# structure_thermometer.net
KiCad netlist of a schematic drawn in Altium Designer
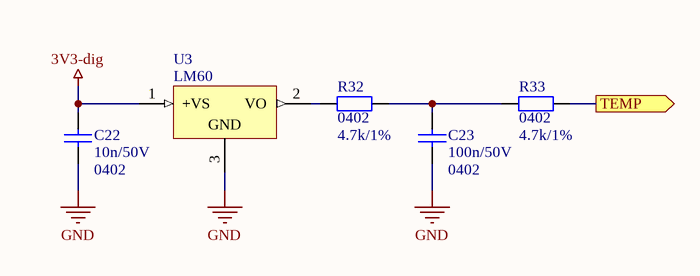
[diagram p0: structure_thermometer.SchDoc]

(export (version "E")
  (design (tool "Eeschema 10.0.6"))
  (components
    (comp (ref "C22")
      (value "10n/50V")
      (footprint "SMD_Capacitor_0402")
      (description "Ceramic Cap Kemet COTS 10n/50V X7R 0402")
      (fields
        (field (name "MANUFACTURERPARTNUMBER") "C0402T103K5RALTU")
        (field (name "MANUFACTURER") "Kemet")
        (field (name "PACKAGE") "0402")
      )
      (libsource (lib "capacitors") (part "Cer_C0402T103K5RALTU"))
    )
    (comp (ref "C23")
      (value "100n/50V")
      (footprint "SMD_Capacitor_0402")
      (description "Ceramic Cap Kemet COTS 10n/50V X7R 0402")
      (fields
        (field (name "MANUFACTURERPARTNUMBER") "C0402T103K5RALTU")
        (field (name "MANUFACTURER") "Kemet")
        (field (name "PACKAGE") "0402")
      )
      (libsource (lib "capacitors") (part "Cer_C0402T103K5RALTU"))
    )
    (comp (ref "R32")
      (value "4.7k/1%")
      (footprint "SMD_Resistor_0402")
      (description "4.7k/1% Vishay CRCW 0402 Resistor. 63mW, 100ppm, 50V.")
      (fields
        (field (name "MANUFACTURERPARTNUMBER") "CRCW04024K70FKxxxx")
        (field (name "MANUFACTURER") "Vishay")
        (field (name "PACKAGE") "0402")
      )
      (libsource (lib "resistors") (part "CRCW04024K70FKxxxx"))
    )
    (comp (ref "R33")
      (value "4.7k/1%")
      (footprint "SMD_Resistor_0402")
      (description "4.7k/1% Vishay CRCW 0402 Resistor. 63mW, 100ppm, 50V.")
      (fields
        (field (name "MANUFACTURERPARTNUMBER") "CRCW04024K70FKxxxx")
        (field (name "MANUFACTURER") "Vishay")
        (field (name "PACKAGE") "0402")
      )
      (libsource (lib "resistors") (part "CRCW04024K70FKxxxx"))
    )
    (comp (ref "U3")
      (value "LM60")
      (footprint "SOT23-3")
      (description "Analog temperature sensor")
      (libsource (lib "microcircuits") (part "LM60"))
    )
  )
  (nets
    (net (code "1") (name "/TEMP") (class "Default")
      (node (ref "R33") (pin "2") (pinfunction "2_2") (pintype "passive"))
    )
    (net (code "2") (name "3V3-dig") (class "Default")
      (node (ref "C22") (pin "1") (pinfunction "1_1") (pintype "passive"))
      (node (ref "U3") (pin "1") (pinfunction "+VS_1") (pintype "input"))
    )
    (net (code "3") (name "GND") (class "Default")
      (node (ref "C22") (pin "2") (pinfunction "2_2") (pintype "passive"))
      (node (ref "C23") (pin "2") (pinfunction "2_2") (pintype "passive"))
      (node (ref "U3") (pin "3") (pinfunction "GND_3") (pintype "power_in"))
    )
    (net (code "4") (name "Net-(C23-Pad1)") (class "Default")
      (node (ref "C23") (pin "1") (pinfunction "1_1") (pintype "passive"))
      (node (ref "R32") (pin "2") (pinfunction "2_2") (pintype "passive"))
      (node (ref "R33") (pin "1") (pinfunction "1_1") (pintype "passive"))
    )
    (net (code "5") (name "Net-(U3-VO)") (class "Default")
      (node (ref "R32") (pin "1") (pinfunction "1_1") (pintype "passive"))
      (node (ref "U3") (pin "2") (pinfunction "VO_2") (pintype "output"))
    )
  )
)
